# 8266_1278.net
KiCad netlist of a schematic drawn in Altium Designer
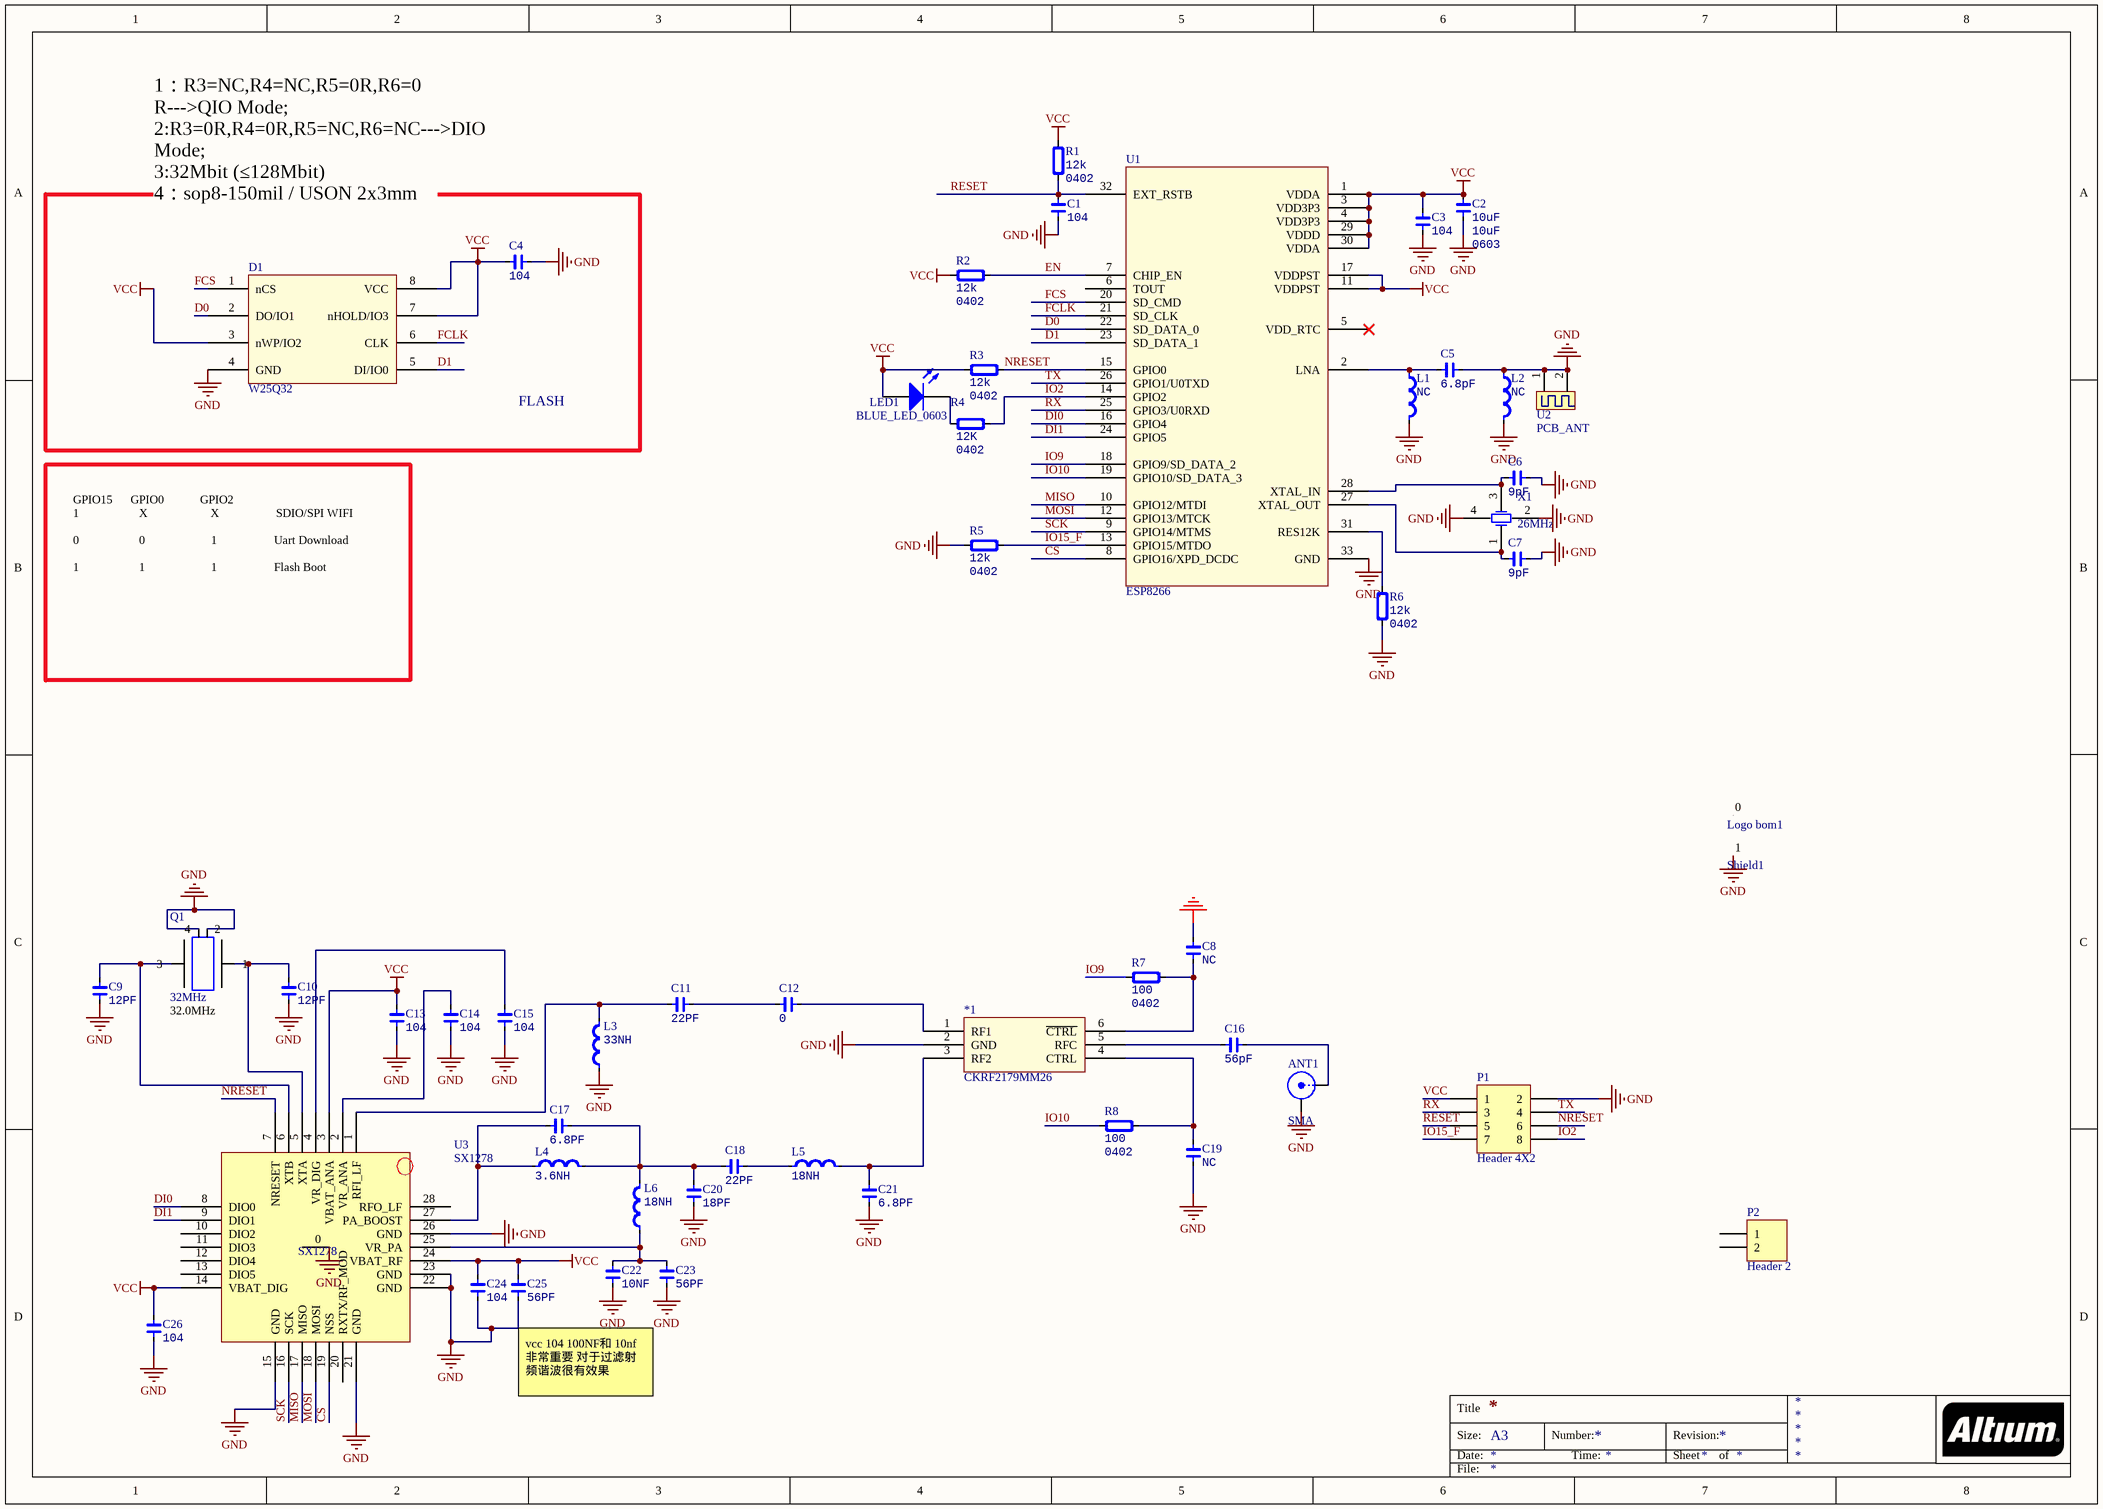
[diagram p0: 网关模块8266_1278.SchDoc]

(export (version "E")
  (design (tool "Eeschema 10.0.6"))
  (components
    (comp (ref "*1")
      (value "CKRF2179MM26")
      (footprint "SC70-6")
      (libsource (lib "SCH_Passive") (part "PE4259"))
    )
    (comp (ref "ANT1")
      (value "SMA")
      (footprint "SMA_EDGE")
      (description "SMA Straight Connector")
      (fields (field (name "PUBLISHER") "Altium Limited"))
      (libsource (lib "SX1301DVK_e286v01a") (part "SMA"))
    )
    (comp (ref "C1")
      (value "104")
      (footprint "PCB_PassiveCap:CAP_0402")
      (description "Capacitor")
      (libsource (lib "SCH_Passive") (part "Cap_0402"))
    )
    (comp (ref "C2")
      (value "10uF")
      (footprint "PCB_PassiveCap:CAP_0603")
      (description "Capacitor")
      (fields (field (name "ALTIUM_VALUE") "10uF") (field (name "TYPE") "0603"))
      (libsource (lib "SCH_Passive") (part "Cap_0603"))
    )
    (comp (ref "C3")
      (value "104")
      (footprint "PCB_PassiveCap:CAP_0402")
      (description "Capacitor")
      (libsource (lib "SCH_Passive") (part "Cap_0402"))
    )
    (comp (ref "C4")
      (value "104")
      (footprint "PCB_PassiveCap:CAP_0402")
      (description "Capacitor")
      (libsource (lib "") (part "Cap_0402_3"))
    )
    (comp (ref "C5")
      (value "6.8pF")
      (footprint "PCB_PassiveCap:CAP_0402")
      (description "Capacitor")
      (libsource (lib "") (part "Cap_0402_1"))
    )
    (comp (ref "C6")
      (value "9pF")
      (footprint "PCB_PassiveCap:CAP_0402")
      (description "Capacitor")
      (libsource (lib "") (part "Cap_0402_1"))
    )
    (comp (ref "C7")
      (value "9pF")
      (footprint "PCB_PassiveCap:CAP_0402")
      (description "Capacitor")
      (libsource (lib "") (part "Cap_0402_1"))
    )
    (comp (ref "C8")
      (value "NC")
      (footprint "PCB_PassiveCap:CAP_0402")
      (description "Capacitor")
      (libsource (lib "") (part "Cap_0402_2"))
    )
    (comp (ref "C9")
      (value "12PF")
      (footprint "PCB_PassiveCap:CAP_0402")
      (description "Capacitor")
      (libsource (lib "SCH_Passive") (part "Cap_0402"))
    )
    (comp (ref "C10")
      (value "12PF")
      (footprint "PCB_PassiveCap:CAP_0402")
      (description "Capacitor")
      (libsource (lib "SCH_Passive") (part "Cap_0402"))
    )
    (comp (ref "C11")
      (value "22PF")
      (footprint "PCB_PassiveCap:CAP_0402")
      (description "Capacitor")
      (libsource (lib "") (part "Cap_0402_1"))
    )
    (comp (ref "C12")
      (value "0")
      (footprint "PCB_PassiveCap:CAP_0402")
      (description "Capacitor")
      (libsource (lib "") (part "Cap_0402_1"))
    )
    (comp (ref "C13")
      (value "104")
      (footprint "PCB_PassiveCap:CAP_0402")
      (description "Capacitor")
      (libsource (lib "SCH_Passive") (part "Cap_0402"))
    )
    (comp (ref "C14")
      (value "104")
      (footprint "PCB_PassiveCap:CAP_0402")
      (description "Capacitor")
      (libsource (lib "SCH_Passive") (part "Cap_0402"))
    )
    (comp (ref "C15")
      (value "104")
      (footprint "PCB_PassiveCap:CAP_0402")
      (description "Capacitor")
      (libsource (lib "SCH_Passive") (part "Cap_0402"))
    )
    (comp (ref "C16")
      (value "56pF")
      (footprint "PCB_PassiveCap:CAP_0402")
      (description "Capacitor")
      (libsource (lib "") (part "Cap_0402_1"))
    )
    (comp (ref "C17")
      (value "6.8PF")
      (footprint "PCB_PassiveCap:CAP_0402")
      (description "Capacitor")
      (libsource (lib "") (part "Cap_0402_1"))
    )
    (comp (ref "C18")
      (value "22PF")
      (footprint "PCB_PassiveCap:CAP_0402")
      (description "Capacitor")
      (libsource (lib "") (part "Cap_0402_1"))
    )
    (comp (ref "C19")
      (value "NC")
      (footprint "PCB_PassiveCap:CAP_0402")
      (description "Capacitor")
      (libsource (lib "") (part "Cap_0402_2"))
    )
    (comp (ref "C20")
      (value "18PF")
      (footprint "PCB_PassiveCap:CAP_0402")
      (description "Capacitor")
      (libsource (lib "SCH_Passive") (part "Cap_0402"))
    )
    (comp (ref "C21")
      (value "6.8PF")
      (footprint "PCB_PassiveCap:CAP_0402")
      (description "Capacitor")
      (libsource (lib "SCH_Passive") (part "Cap_0402"))
    )
    (comp (ref "C22")
      (value "10NF")
      (footprint "PCB_PassiveCap:CAP_0402")
      (description "Capacitor")
      (libsource (lib "SCH_Passive") (part "Cap_0402"))
    )
    (comp (ref "C23")
      (value "56PF")
      (footprint "PCB_PassiveCap:CAP_0402")
      (description "Capacitor")
      (libsource (lib "SCH_Passive") (part "Cap_0402"))
    )
    (comp (ref "C24")
      (value "104")
      (footprint "PCB_PassiveCap:CAP_0402")
      (description "Capacitor")
      (libsource (lib "SCH_Passive") (part "Cap_0402"))
    )
    (comp (ref "C25")
      (value "56PF")
      (footprint "PCB_PassiveCap:CAP_0402")
      (description "Capacitor")
      (libsource (lib "SCH_Passive") (part "Cap_0402"))
    )
    (comp (ref "C26")
      (value "104")
      (footprint "PCB_PassiveCap:CAP_0402")
      (description "Capacitor")
      (libsource (lib "") (part "Cap_0402_2"))
    )
    (comp (ref "D1") (value "W25Q32") (footprint "W25Q128-1") (libsource (lib "ESP8266") (part "W25Q128")))
    (comp (ref "L1")
      (value "NC")
      (footprint "PCB_PassiveInd:IND_0402")
      (description "Inductor")
      (libsource (lib "SCH_Passive") (part "Ind_0402"))
    )
    (comp (ref "L2")
      (value "NC")
      (footprint "PCB_PassiveInd:IND_0402")
      (description "Inductor")
      (libsource (lib "SCH_Passive") (part "Ind_0402"))
    )
    (comp (ref "L3")
      (value "33NH")
      (footprint "PCB_PassiveInd:IND_0402")
      (description "Inductor")
      (libsource (lib "SCH_Passive") (part "Ind_0402"))
    )
    (comp (ref "L4")
      (value "3.6NH")
      (footprint "PCB_PassiveInd:IND_0402")
      (description "Inductor")
      (libsource (lib "SCH_Passive") (part "Ind_0402"))
    )
    (comp (ref "L5")
      (value "18NH")
      (footprint "PCB_PassiveInd:IND_0402")
      (description "Inductor")
      (libsource (lib "SCH_Passive") (part "Ind_0402"))
    )
    (comp (ref "L6")
      (value "18NH")
      (footprint "PCB_PassiveInd:IND_0402")
      (description "Inductor")
      (libsource (lib "SCH_Passive") (part "Ind_0402"))
    )
    (comp (ref "LED1")
      (value "BLUE_LED_0603")
      (footprint "SMDLED")
      (description "Typical RED, GREEN, YELLOW, AMBER GaAs LED")
      (fields (field (name "PUBLISHER") "Altium Limited"))
      (libsource (lib "ESP8266") (part "LED2"))
    )
    (comp (ref "Logo bom1")
      (value "Logo symbol")
      (footprint "logo1")
      (description "qc symbol for Logo")
      (libsource (lib "SX1301DVK_e286v01a") (part "Logo"))
    )
    (comp (ref "P1")
      (value "Header 4X2")
      (footprint "MY HDR 2X4")
      (description "Header, 4-Pin, Dual row")
      (fields (field (name "PUBLISHER") "Altium Limited"))
      (libsource (lib "Miscellaneous Connectors") (part "Header 4X2"))
    )
    (comp (ref "P2")
      (value "Header 2")
      (footprint "HDR1X2")
      (description "Header, 2-Pin")
      (fields (field (name "PUBLISHER") "Altium Limited"))
      (libsource (lib "Miscellaneous Connectors") (part "Header 2"))
    )
    (comp (ref "Q1")
      (value "32MHz")
      (footprint "3325")
      (description "32M无源晶振 10PPM   年老化3ppm以内")
      (fields (field (name "ALTIUM_VALUE") "32.0MHz"))
      (libsource (lib "SX1301DVK_e286v01a") (part "Xtal GND"))
    )
    (comp (ref "R1")
      (value "12k")
      (footprint "PCB_PassiveRes:RES_0402")
      (description "Resistor")
      (fields (field (name "TYPE") "0402") (field (name "Comment") "12K"))
      (libsource (lib "SCH_Passive") (part "Res_0402"))
    )
    (comp (ref "R2")
      (value "12k")
      (footprint "PCB_PassiveRes:RES_0402")
      (description "Resistor")
      (fields (field (name "TYPE") "0402") (field (name "Comment") "12K"))
      (libsource (lib "SCH_Passive") (part "Res_0402"))
    )
    (comp (ref "R3")
      (value "12k")
      (footprint "PCB_PassiveRes:RES_0402")
      (description "Resistor")
      (fields (field (name "TYPE") "0402") (field (name "Comment") "12K"))
      (libsource (lib "SCH_Passive") (part "Res_0402"))
    )
    (comp (ref "R4")
      (value "12K")
      (footprint "PCB_PassiveRes:RES_0402")
      (description "Resistor")
      (fields (field (name "TYPE") "0402") (field (name "Comment") "820"))
      (libsource (lib "SCH_Passive") (part "Res_0402"))
    )
    (comp (ref "R5")
      (value "12k")
      (footprint "PCB_PassiveRes:RES_0402")
      (description "Resistor")
      (fields (field (name "TYPE") "0402") (field (name "Comment") "12K"))
      (libsource (lib "SCH_Passive") (part "Res_0402"))
    )
    (comp (ref "R6")
      (value "12k")
      (footprint "PCB_PassiveRes:RES_0402")
      (description "Resistor")
      (fields (field (name "TYPE") "0402") (field (name "Comment") "12K"))
      (libsource (lib "SCH_Passive") (part "Res_0402"))
    )
    (comp (ref "R7")
      (value "100")
      (footprint "PCB_PassiveRes:RES_0402")
      (description "Resistor")
      (fields (field (name "TYPE") "0402"))
      (libsource (lib "SCH_Passive") (part "Res_0402"))
    )
    (comp (ref "R8")
      (value "100")
      (footprint "PCB_PassiveRes:RES_0402")
      (description "Resistor")
      (fields (field (name "TYPE") "0402"))
      (libsource (lib "SCH_Passive") (part "Res_0402"))
    )
    (comp (ref "Shield1")
      (value "Logo symbol")
      (footprint "24*18_8266")
      (description "Shield - EMI Gasket - Standard Surface Mount Shields")
      (libsource (lib "SX1301DVK_e286v01a") (part "Shield"))
    )
    (comp (ref "U1") (value "ESP8266") (footprint "ESP8266") (libsource (lib "ESP8266") (part "ESP8266")))
    (comp (ref "U2") (value "PCB_ANT") (footprint "BLE-ANT4") (libsource (lib "ESP8266") (part "天线")))
    (comp (ref "U3") (value "SX1278") (footprint "QFN-28") (libsource (lib "C-M001-32_V1.0") (part "SX1278")))
    (comp (ref "X1")
      (value "26MHz")
      (footprint "CY_3225")
      (description "24M无源晶振（10ppm）")
      (fields (field (name "PUBLISHER") "Altium Limited"))
      (libsource (lib "ESP8266") (part "XTAL"))
    )
  )
  (nets
    (net (code "1") (name "/CS") (class "Default")
      (node (ref "U1") (pin "8") (pinfunction "GPIO16/XPD_DCDC_8") (pintype "passive"))
      (node (ref "U3") (pin "19") (pinfunction "NSS_19") (pintype "passive"))
    )
    (net (code "2") (name "/D0") (class "Default")
      (node (ref "D1") (pin "2") (pinfunction "DO/IO1_2") (pintype "passive"))
      (node (ref "U1") (pin "22") (pinfunction "SD_DATA_0_22") (pintype "passive"))
    )
    (net (code "3") (name "/D1") (class "Default")
      (node (ref "D1") (pin "5") (pinfunction "DI/IO0_5") (pintype "passive"))
      (node (ref "U1") (pin "23") (pinfunction "SD_DATA_1_23") (pintype "passive"))
    )
    (net (code "4") (name "/DI0") (class "Default")
      (node (ref "U1") (pin "16") (pinfunction "GPIO4_16") (pintype "passive"))
      (node (ref "U3") (pin "8") (pinfunction "DIO0_8") (pintype "passive"))
    )
    (net (code "5") (name "/DI1") (class "Default")
      (node (ref "U1") (pin "24") (pinfunction "GPIO5_24") (pintype "passive"))
      (node (ref "U3") (pin "9") (pinfunction "DIO1_9") (pintype "passive"))
    )
    (net (code "6") (name "/EN") (class "Default")
      (node (ref "R2") (pin "1") (pinfunction "1_1") (pintype "passive"))
      (node (ref "U1") (pin "7") (pinfunction "CHIP_EN_7") (pintype "passive"))
    )
    (net (code "7") (name "/FCLK") (class "Default")
      (node (ref "D1") (pin "6") (pinfunction "CLK_6") (pintype "passive"))
      (node (ref "U1") (pin "21") (pinfunction "SD_CLK_21") (pintype "passive"))
    )
    (net (code "8") (name "/FCS") (class "Default")
      (node (ref "D1") (pin "1") (pinfunction "nCS_1") (pintype "passive"))
      (node (ref "U1") (pin "20") (pinfunction "SD_CMD_20") (pintype "passive"))
    )
    (net (code "9") (name "/IO2") (class "Default")
      (node (ref "P1") (pin "8") (pinfunction "8_8") (pintype "passive"))
      (node (ref "R4") (pin "1") (pinfunction "1_1") (pintype "passive"))
      (node (ref "U1") (pin "14") (pinfunction "GPIO2_14") (pintype "passive"))
    )
    (net (code "10") (name "/IO9") (class "Default")
      (node (ref "R7") (pin "1") (pinfunction "1_1") (pintype "passive"))
      (node (ref "U1") (pin "18") (pinfunction "GPIO9/SD_DATA_2_18") (pintype "passive"))
    )
    (net (code "11") (name "/IO10") (class "Default")
      (node (ref "R8") (pin "1") (pinfunction "1_1") (pintype "passive"))
      (node (ref "U1") (pin "19") (pinfunction "GPIO10/SD_DATA_3_19") (pintype "passive"))
    )
    (net (code "12") (name "/IO15_F") (class "Default")
      (node (ref "P1") (pin "7") (pinfunction "7_7") (pintype "passive"))
      (node (ref "R5") (pin "1") (pinfunction "1_1") (pintype "passive"))
      (node (ref "U1") (pin "13") (pinfunction "GPIO15/MTDO_13") (pintype "passive"))
    )
    (net (code "13") (name "/MISO") (class "Default")
      (node (ref "U1") (pin "10") (pinfunction "GPIO12/MTDI_10") (pintype "passive"))
      (node (ref "U3") (pin "17") (pinfunction "MISO_17") (pintype "passive"))
    )
    (net (code "14") (name "/MOSI") (class "Default")
      (node (ref "U1") (pin "12") (pinfunction "GPIO13/MTCK_12") (pintype "passive"))
      (node (ref "U3") (pin "18") (pinfunction "MOSI_18") (pintype "passive"))
    )
    (net (code "15") (name "/NRESET") (class "Default")
      (node (ref "P1") (pin "6") (pinfunction "6_6") (pintype "passive"))
      (node (ref "R3") (pin "1") (pinfunction "1_1") (pintype "passive"))
      (node (ref "U1") (pin "15") (pinfunction "GPIO0_15") (pintype "passive"))
      (node (ref "U3") (pin "7") (pinfunction "NRESET_7") (pintype "passive"))
    )
    (net (code "16") (name "/RESET") (class "Default")
      (node (ref "C1") (pin "2") (pinfunction "2_2") (pintype "passive"))
      (node (ref "P1") (pin "5") (pinfunction "5_5") (pintype "passive"))
      (node (ref "R1") (pin "1") (pinfunction "1_1") (pintype "passive"))
      (node (ref "U1") (pin "32") (pinfunction "EXT_RSTB_32") (pintype "passive"))
    )
    (net (code "17") (name "/RX") (class "Default")
      (node (ref "P1") (pin "3") (pinfunction "3_3") (pintype "passive"))
      (node (ref "U1") (pin "25") (pinfunction "GPIO3/U0RXD_25") (pintype "passive"))
    )
    (net (code "18") (name "/SCK") (class "Default")
      (node (ref "U1") (pin "9") (pinfunction "GPIO14/MTMS_9") (pintype "passive"))
      (node (ref "U3") (pin "16") (pinfunction "SCK_16") (pintype "passive"))
    )
    (net (code "19") (name "/TX") (class "Default")
      (node (ref "P1") (pin "4") (pinfunction "4_4") (pintype "passive"))
      (node (ref "U1") (pin "26") (pinfunction "GPIO1/U0TXD_26") (pintype "passive"))
    )
    (net (code "20") (name "GND") (class "Default")
      (node (ref "*1") (pin "2") (pinfunction "GND_2") (pintype "passive"))
      (node (ref "ANT1") (pin "2") (pinfunction "GND_2") (pintype "passive"))
      (node (ref "C1") (pin "1") (pinfunction "1_1") (pintype "passive"))
      (node (ref "C10") (pin "1") (pinfunction "1_1") (pintype "passive"))
      (node (ref "C13") (pin "1") (pinfunction "1_1") (pintype "passive"))
      (node (ref "C14") (pin "1") (pinfunction "1_1") (pintype "passive"))
      (node (ref "C15") (pin "1") (pinfunction "1_1") (pintype "passive"))
      (node (ref "C19") (pin "2") (pinfunction "2_2") (pintype "passive"))
      (node (ref "C2") (pin "1") (pinfunction "1_1") (pintype "passive"))
      (node (ref "C20") (pin "1") (pinfunction "1_1") (pintype "passive"))
      (node (ref "C21") (pin "1") (pinfunction "1_1") (pintype "passive"))
      (node (ref "C22") (pin "1") (pinfunction "1_1") (pintype "passive"))
      (node (ref "C23") (pin "1") (pinfunction "1_1") (pintype "passive"))
      (node (ref "C24") (pin "1") (pinfunction "1_1") (pintype "passive"))
      (node (ref "C25") (pin "1") (pinfunction "1_1") (pintype "passive"))
      (node (ref "C26") (pin "2") (pinfunction "2_2") (pintype "passive"))
      (node (ref "C3") (pin "1") (pinfunction "1_1") (pintype "passive"))
      (node (ref "C4") (pin "2") (pinfunction "2_2") (pintype "passive"))
      (node (ref "C5") (pin "1") (pinfunction "1_1") (pintype "passive"))
      (node (ref "C6") (pin "1") (pinfunction "1_1") (pintype "passive"))
      (node (ref "C7") (pin "1") (pinfunction "1_1") (pintype "passive"))
      (node (ref "C8") (pin "1") (pinfunction "1_1") (pintype "passive"))
      (node (ref "C9") (pin "1") (pinfunction "1_1") (pintype "passive"))
      (node (ref "D1") (pin "4") (pinfunction "GND_4") (pintype "passive"))
      (node (ref "L1") (pin "2") (pinfunction "2_2") (pintype "passive"))
      (node (ref "L2") (pin "1") (pinfunction "1_1") (pintype "passive"))
      (node (ref "L2") (pin "2") (pinfunction "2_2") (pintype "passive"))
      (node (ref "L3") (pin "1") (pinfunction "1_1") (pintype "passive"))
      (node (ref "P1") (pin "2") (pinfunction "2_2") (pintype "passive"))
      (node (ref "Q1") (pin "2") (pinfunction "2_2") (pintype "passive"))
      (node (ref "Q1") (pin "4") (pinfunction "4_4") (pintype "passive"))
      (node (ref "R5") (pin "2") (pinfunction "2_2") (pintype "passive"))
      (node (ref "R6") (pin "2") (pinfunction "2_2") (pintype "passive"))
      (node (ref "Shield1") (pin "1") (pinfunction "1_1") (pintype "passive"))
      (node (ref "U1") (pin "33") (pinfunction "GND_33") (pintype "passive"))
      (node (ref "U2") (pin "1") (pintype "passive"))
      (node (ref "U2") (pin "2") (pintype "passive"))
      (node (ref "U3") (pin "0") (pinfunction "0_0") (pintype "passive"))
      (node (ref "U3") (pin "15") (pinfunction "GND_15") (pintype "passive"))
      (node (ref "U3") (pin "21") (pinfunction "GND_21") (pintype "passive"))
      (node (ref "U3") (pin "22") (pinfunction "GND_22") (pintype "passive"))
      (node (ref "U3") (pin "23") (pinfunction "GND_23") (pintype "passive"))
      (node (ref "U3") (pin "26") (pinfunction "GND_26") (pintype "passive"))
      (node (ref "X1") (pin "2") (pinfunction "OSC2_2") (pintype "passive"))
      (node (ref "X1") (pin "4") (pinfunction "OSC2_4") (pintype "passive"))
    )
    (net (code "21") (name "Net-(*1-CTRL)") (class "Default")
      (node (ref "*1") (pin "4") (pinfunction "CTRL_4") (pintype "passive"))
      (node (ref "C19") (pin "1") (pinfunction "1_1") (pintype "passive"))
      (node (ref "R8") (pin "2") (pinfunction "2_2") (pintype "passive"))
    )
    (net (code "22") (name "Net-(*1-RF1)") (class "Default")
      (node (ref "*1") (pin "1") (pinfunction "RF1_1") (pintype "passive"))
      (node (ref "C12") (pin "1") (pinfunction "1_1") (pintype "passive"))
    )
    (net (code "23") (name "Net-(*1-RF2)") (class "Default")
      (node (ref "*1") (pin "3") (pinfunction "RF2_3") (pintype "passive"))
      (node (ref "C21") (pin "2") (pinfunction "2_2") (pintype "passive"))
      (node (ref "L5") (pin "2") (pinfunction "2_2") (pintype "passive"))
    )
    (net (code "24") (name "Net-(*1-RFC)") (class "Default")
      (node (ref "*1") (pin "5") (pinfunction "RFC_5") (pintype "passive"))
      (node (ref "C16") (pin "2") (pinfunction "2_2") (pintype "passive"))
    )
    (net (code "25") (name "Net-(*1-~{CTRL})") (class "Default")
      (node (ref "*1") (pin "6") (pinfunction "~{CTRL}_6") (pintype "passive"))
      (node (ref "C8") (pin "2") (pinfunction "2_2") (pintype "passive"))
      (node (ref "R7") (pin "2") (pinfunction "2_2") (pintype "passive"))
    )
    (net (code "26") (name "Net-(ANT1-Signal)") (class "Default")
      (node (ref "ANT1") (pin "1") (pinfunction "Signal_1") (pintype "passive"))
      (node (ref "C16") (pin "1") (pinfunction "1_1") (pintype "passive"))
    )
    (net (code "27") (name "Net-(C11-Pad1)") (class "Default")
      (node (ref "C11") (pin "1") (pinfunction "1_1") (pintype "passive"))
      (node (ref "C12") (pin "2") (pinfunction "2_2") (pintype "passive"))
    )
    (net (code "28") (name "Net-(C17-Pad1)") (class "Default")
      (node (ref "C17") (pin "1") (pinfunction "1_1") (pintype "passive"))
      (node (ref "C18") (pin "2") (pinfunction "2_2") (pintype "passive"))
      (node (ref "C20") (pin "2") (pinfunction "2_2") (pintype "passive"))
      (node (ref "L4") (pin "2") (pinfunction "2_2") (pintype "passive"))
      (node (ref "L6") (pin "2") (pinfunction "2_2") (pintype "passive"))
    )
    (net (code "29") (name "Net-(C18-Pad1)") (class "Default")
      (node (ref "C18") (pin "1") (pinfunction "1_1") (pintype "passive"))
      (node (ref "L5") (pin "1") (pinfunction "1_1") (pintype "passive"))
    )
    (net (code "30") (name "Net-(LED1-K)") (class "Default")
      (node (ref "LED1") (pin "2") (pinfunction "K_2") (pintype "passive"))
      (node (ref "R4") (pin "2") (pinfunction "2_2") (pintype "passive"))
    )
    (net (code "31") (name "Net-(U1-LNA)") (class "Default")
      (node (ref "C5") (pin "2") (pinfunction "2_2") (pintype "passive"))
      (node (ref "L1") (pin "1") (pinfunction "1_1") (pintype "passive"))
      (node (ref "U1") (pin "2") (pinfunction "LNA_2") (pintype "passive"))
    )
    (net (code "32") (name "Net-(U1-RES12K)") (class "Default")
      (node (ref "R6") (pin "1") (pinfunction "1_1") (pintype "passive"))
      (node (ref "U1") (pin "31") (pinfunction "RES12K_31") (pintype "passive"))
    )
    (net (code "33") (name "Net-(U1-XTAL_IN)") (class "Default")
      (node (ref "C6") (pin "2") (pinfunction "2_2") (pintype "passive"))
      (node (ref "U1") (pin "28") (pinfunction "XTAL_IN_28") (pintype "passive"))
      (node (ref "X1") (pin "3") (pinfunction "OSC2_3") (pintype "passive"))
    )
    (net (code "34") (name "Net-(U1-XTAL_OUT)") (class "Default")
      (node (ref "C7") (pin "2") (pinfunction "2_2") (pintype "passive"))
      (node (ref "U1") (pin "27") (pinfunction "XTAL_OUT_27") (pintype "passive"))
      (node (ref "X1") (pin "1") (pinfunction "OSC1_1") (pintype "passive"))
    )
    (net (code "35") (name "Net-(U3-PA_BOOST)") (class "Default")
      (node (ref "C17") (pin "2") (pinfunction "2_2") (pintype "passive"))
      (node (ref "L4") (pin "1") (pinfunction "1_1") (pintype "passive"))
      (node (ref "U3") (pin "27") (pinfunction "PA_BOOST_27") (pintype "passive"))
    )
    (net (code "36") (name "Net-(U3-RFI_LF)") (class "Default")
      (node (ref "C11") (pin "2") (pinfunction "2_2") (pintype "passive"))
      (node (ref "L3") (pin "2") (pinfunction "2_2") (pintype "passive"))
      (node (ref "U3") (pin "1") (pinfunction "RFI_LF_1") (pintype "passive"))
    )
    (net (code "37") (name "Net-(U3-VR_ANA)") (class "Default")
      (node (ref "C14") (pin "2") (pinfunction "2_2") (pintype "passive"))
      (node (ref "U3") (pin "2") (pinfunction "VR_ANA_2") (pintype "passive"))
    )
    (net (code "38") (name "Net-(U3-VR_DIG)") (class "Default")
      (node (ref "C15") (pin "2") (pinfunction "2_2") (pintype "passive"))
      (node (ref "U3") (pin "4") (pinfunction "VR_DIG_4") (pintype "passive"))
    )
    (net (code "39") (name "Net-(U3-VR_PA)") (class "Default")
      (node (ref "C22") (pin "2") (pinfunction "2_2") (pintype "passive"))
      (node (ref "C23") (pin "2") (pinfunction "2_2") (pintype "passive"))
      (node (ref "L6") (pin "1") (pinfunction "1_1") (pintype "passive"))
      (node (ref "U3") (pin "25") (pinfunction "VR_PA_25") (pintype "passive"))
    )
    (net (code "40") (name "Net-(U3-XTA)") (class "Default")
      (node (ref "C10") (pin "2") (pinfunction "2_2") (pintype "passive"))
      (node (ref "Q1") (pin "1") (pinfunction "1_1") (pintype "passive"))
      (node (ref "U3") (pin "5") (pinfunction "XTA_5") (pintype "passive"))
    )
    (net (code "41") (name "Net-(U3-XTB)") (class "Default")
      (node (ref "C9") (pin "2") (pinfunction "2_2") (pintype "passive"))
      (node (ref "Q1") (pin "3") (pinfunction "3_3") (pintype "passive"))
      (node (ref "U3") (pin "6") (pinfunction "XTB_6") (pintype "passive"))
    )
    (net (code "42") (name "VCC") (class "Default")
      (node (ref "C13") (pin "2") (pinfunction "2_2") (pintype "passive"))
      (node (ref "C2") (pin "2") (pinfunction "2_2") (pintype "passive"))
      (node (ref "C24") (pin "2") (pinfunction "2_2") (pintype "passive"))
      (node (ref "C25") (pin "2") (pinfunction "2_2") (pintype "passive"))
      (node (ref "C26") (pin "1") (pinfunction "1_1") (pintype "passive"))
      (node (ref "C3") (pin "2") (pinfunction "2_2") (pintype "passive"))
      (node (ref "C4") (pin "1") (pinfunction "1_1") (pintype "passive"))
      (node (ref "D1") (pin "3") (pinfunction "nWP/IO2_3") (pintype "passive"))
      (node (ref "D1") (pin "7") (pinfunction "nHOLD/IO3_7") (pintype "passive"))
      (node (ref "D1") (pin "8") (pinfunction "VCC_8") (pintype "passive"))
      (node (ref "LED1") (pin "1") (pinfunction "A_1") (pintype "passive"))
      (node (ref "P1") (pin "1") (pinfunction "1_1") (pintype "passive"))
      (node (ref "R1") (pin "2") (pinfunction "2_2") (pintype "passive"))
      (node (ref "R2") (pin "2") (pinfunction "2_2") (pintype "passive"))
      (node (ref "R3") (pin "2") (pinfunction "2_2") (pintype "passive"))
      (node (ref "U1") (pin "1") (pinfunction "VDDA_1") (pintype "passive"))
      (node (ref "U1") (pin "11") (pinfunction "VDDPST_11") (pintype "passive"))
      (node (ref "U1") (pin "17") (pinfunction "VDDPST_17") (pintype "passive"))
      (node (ref "U1") (pin "29") (pinfunction "VDDD_29") (pintype "passive"))
      (node (ref "U1") (pin "3") (pinfunction "VDD3P3_3") (pintype "passive"))
      (node (ref "U1") (pin "30") (pinfunction "VDDA_30") (pintype "passive"))
      (node (ref "U1") (pin "4") (pinfunction "VDD3P3_4") (pintype "passive"))
      (node (ref "U3") (pin "14") (pinfunction "VBAT_DIG_14") (pintype "passive"))
      (node (ref "U3") (pin "24") (pinfunction "VBAT_RF_24") (pintype "passive"))
      (node (ref "U3") (pin "3") (pinfunction "VBAT_ANA_3") (pintype "passive"))
    )
    (net (code "43") (name "unconnected-(Logo bom1-Pad0)") (class "Default")
      (node (ref "Logo bom1") (pin "0") (pinfunction "0_0") (pintype "passive"))
    )
    (net (code "44") (name "unconnected-(P2-Pad1)") (class "Default")
      (node (ref "P2") (pin "1") (pinfunction "1_1") (pintype "passive"))
    )
    (net (code "45") (name "unconnected-(P2-Pad2)") (class "Default")
      (node (ref "P2") (pin "2") (pinfunction "2_2") (pintype "passive"))
    )
    (net (code "46") (name "unconnected-(U1-TOUT-Pad6)") (class "Default")
      (node (ref "U1") (pin "6") (pinfunction "TOUT_6") (pintype "passive"))
    )
    (net (code "47") (name "unconnected-(U1-VDD_RTC-Pad5)") (class "Default")
      (node (ref "U1") (pin "5") (pinfunction "VDD_RTC_5") (pintype "passive+no_connect"))
    )
    (net (code "48") (name "unconnected-(U3-DIO2-Pad10)") (class "Default")
      (node (ref "U3") (pin "10") (pinfunction "DIO2_10") (pintype "passive"))
    )
    (net (code "49") (name "unconnected-(U3-DIO3-Pad11)") (class "Default")
      (node (ref "U3") (pin "11") (pinfunction "DIO3_11") (pintype "passive"))
    )
    (net (code "50") (name "unconnected-(U3-DIO4-Pad12)") (class "Default")
      (node (ref "U3") (pin "12") (pinfunction "DIO4_12") (pintype "passive"))
    )
    (net (code "51") (name "unconnected-(U3-DIO5-Pad13)") (class "Default")
      (node (ref "U3") (pin "13") (pinfunction "DIO5_13") (pintype "passive"))
    )
    (net (code "52") (name "unconnected-(U3-RFO_LF-Pad28)") (class "Default")
      (node (ref "U3") (pin "28") (pinfunction "RFO_LF_28") (pintype "passive"))
    )
    (net (code "53") (name "unconnected-(U3-RXTX{slash}RF_MOD-Pad20)") (class "Default")
      (node (ref "U3") (pin "20") (pinfunction "RXTX/RF_MOD_20") (pintype "passive"))
    )
  )
)
